# FLASH.net
KiCad netlist of a schematic drawn in Altium Designer
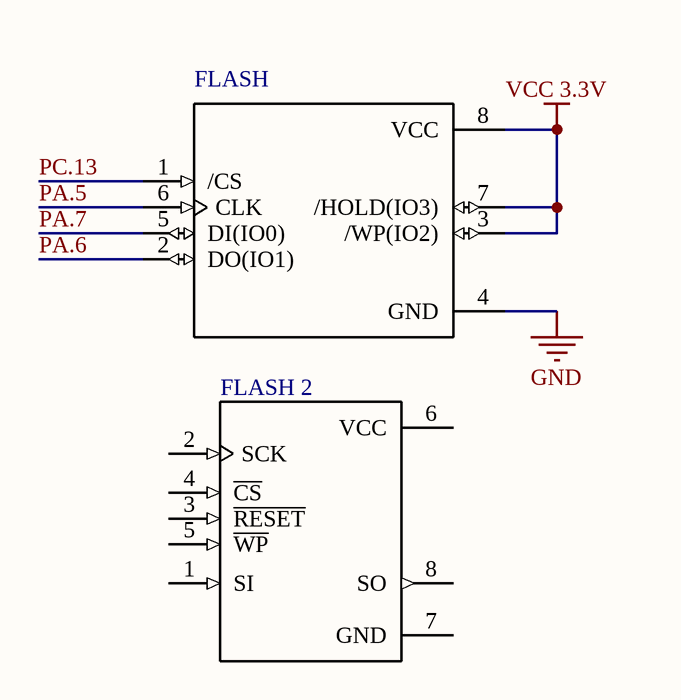
[diagram p0: FLASH.SchDoc]

(export (version "E")
  (design (tool "Eeschema 10.0.6"))
  (components
    (comp (ref "FLASH")
      (value "W25Q16BVSSIG")
      (footprint "*SOIC127P790X216-8N")
      (description "Flash, pin, soic, flash, Memory, Semiconductors and Actives, serial, ic")
      (fields (field (name "MF") "Winbond"))
      (libsource (lib "W25Q16BVSSIG") (part "W25Q16BVSSIG"))
    )
    (comp (ref "FLASH 2")
      (value "AT45DB041E-SSHNHA-T")
      (footprint "*SOIC127P600X175-8N")
      (description "Memory: Serial Flash; 4Mbit; SPI / RapidS; 85MHz; 1.65Ã·3.6V; SO8")
      (fields (field (name "MF") "Adesto"))
      (libsource (lib "AT45DB041E-SSHNHA-T") (part "AT45DB041E-SSHNHA-T"))
    )
  )
  (nets
    (net (code "1") (name "/PA.5") (class "Default")
      (node (ref "FLASH") (pin "6") (pinfunction "CLK_6") (pintype "input"))
    )
    (net (code "2") (name "/PA.6") (class "Default")
      (node (ref "FLASH") (pin "2") (pinfunction "DO(IO1)_2") (pintype "bidirectional"))
    )
    (net (code "3") (name "/PA.7") (class "Default")
      (node (ref "FLASH") (pin "5") (pinfunction "DI(IO0)_5") (pintype "bidirectional"))
    )
    (net (code "4") (name "/PC.13") (class "Default")
      (node (ref "FLASH") (pin "1") (pinfunction "/CS_1") (pintype "input"))
    )
    (net (code "5") (name "GND") (class "Default")
      (node (ref "FLASH") (pin "4") (pinfunction "GND_4") (pintype "power_in"))
    )
    (net (code "6") (name "VCC 3.3V") (class "Default")
      (node (ref "FLASH") (pin "3") (pinfunction "/WP(IO2)_3") (pintype "bidirectional"))
      (node (ref "FLASH") (pin "7") (pinfunction "/HOLD(IO3)_7") (pintype "bidirectional"))
      (node (ref "FLASH") (pin "8") (pinfunction "VCC_8") (pintype "power_in"))
    )
    (net (code "7") (name "unconnected-(FLASH 2-GND-Pad7)") (class "Default")
      (node (ref "FLASH 2") (pin "7") (pinfunction "GND_7") (pintype "passive"))
    )
    (net (code "8") (name "unconnected-(FLASH 2-SCK-Pad2)") (class "Default")
      (node (ref "FLASH 2") (pin "2") (pinfunction "SCK_2") (pintype "input"))
    )
    (net (code "9") (name "unconnected-(FLASH 2-SI-Pad1)") (class "Default")
      (node (ref "FLASH 2") (pin "1") (pinfunction "SI_1") (pintype "input"))
    )
    (net (code "10") (name "unconnected-(FLASH 2-SO-Pad8)") (class "Default")
      (node (ref "FLASH 2") (pin "8") (pinfunction "SO_8") (pintype "output"))
    )
    (net (code "11") (name "unconnected-(FLASH 2-VCC-Pad6)") (class "Default")
      (node (ref "FLASH 2") (pin "6") (pinfunction "VCC_6") (pintype "power_in"))
    )
    (net (code "12") (name "unconnected-(FLASH 2-~{CS}-Pad4)") (class "Default")
      (node (ref "FLASH 2") (pin "4") (pinfunction "~{CS}_4") (pintype "input"))
    )
    (net (code "13") (name "unconnected-(FLASH 2-~{RESET}-Pad3)") (class "Default")
      (node (ref "FLASH 2") (pin "3") (pinfunction "~{RESET}_3") (pintype "input"))
    )
    (net (code "14") (name "unconnected-(FLASH 2-~{WP}-Pad5)") (class "Default")
      (node (ref "FLASH 2") (pin "5") (pinfunction "~{WP}_5") (pintype "input"))
    )
  )
)
